# DATN_Schematic.net
KiCad netlist of a schematic drawn in Altium Designer
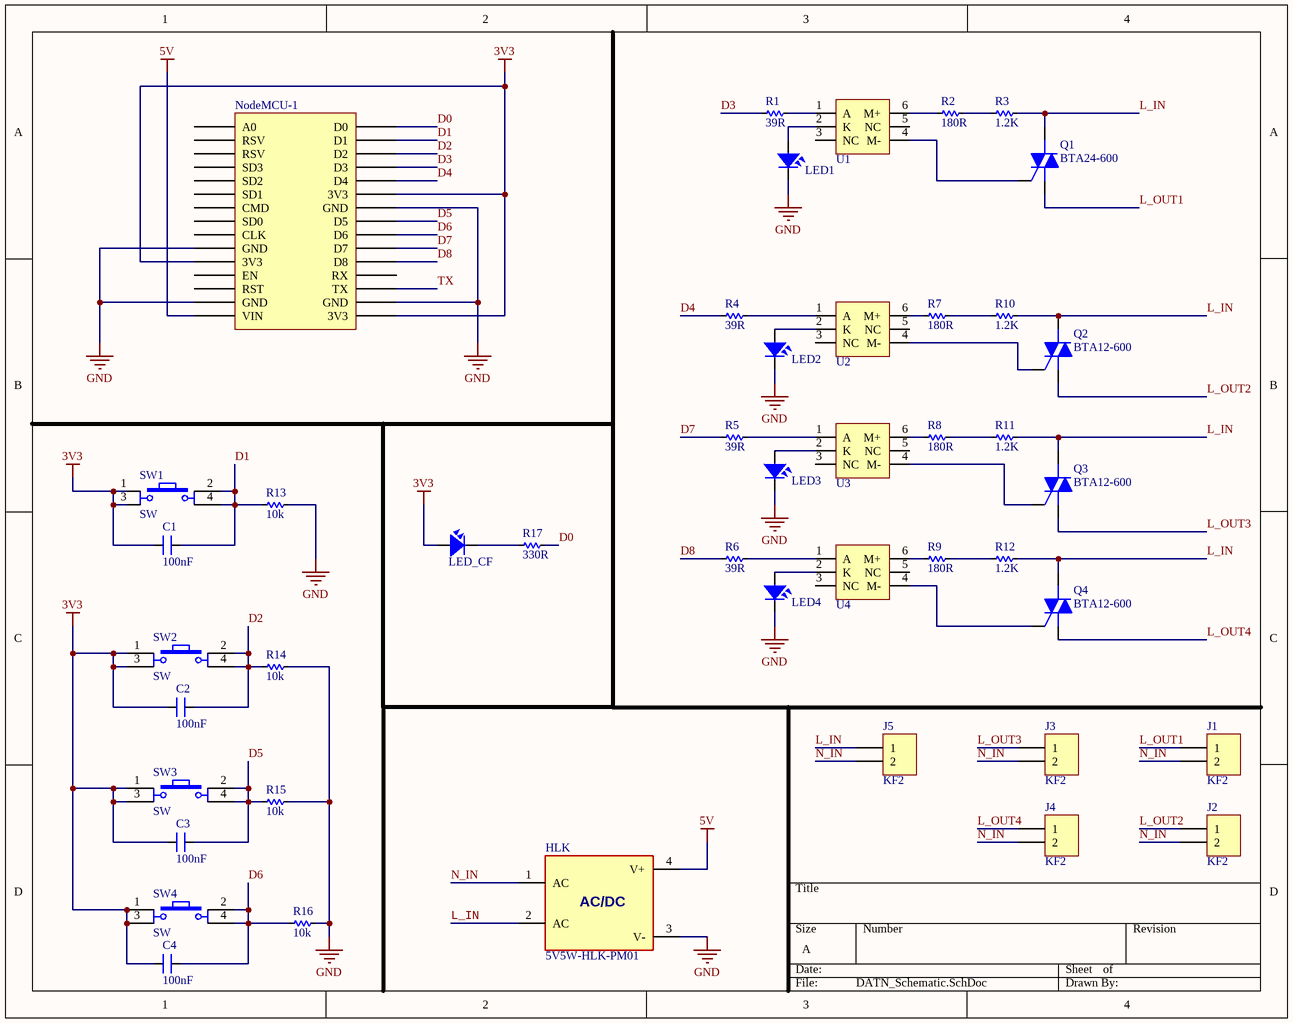
[diagram p0: DATN_Schematic.SchDoc]

(export (version "E")
  (design (tool "Eeschema 10.0.6"))
  (components
    (comp (ref "C1") (value "100nF") (footprint "CN1.5") (libsource (lib "LIBRARY_mualinhkien") (part "CN")))
    (comp (ref "C2") (value "100nF") (footprint "CN1.5") (libsource (lib "LIBRARY_mualinhkien") (part "CN")))
    (comp (ref "C3") (value "100nF") (footprint "CN1.5") (libsource (lib "LIBRARY_mualinhkien") (part "CN")))
    (comp (ref "C4") (value "100nF") (footprint "CN1.5") (libsource (lib "LIBRARY_mualinhkien") (part "CN")))
    (comp (ref "HLK")
      (value "5V5W-HLK-PM01")
      (footprint "HLK_PM01 5V3W")
      (libsource (lib "Duc") (part "5V3W-HLK-PM01"))
    )
    (comp (ref "J1")
      (value "KF2")
      (footprint "KF2-5.08")
      (fields
        (field (name "MANUFACTURER") "Würth Elektronik eiSos GmbH")
        (field (name "PARTNO") "691103110002")
        (field (name "CREATED BY") "Karrer Zheng")
      )
      (libsource (lib "LIBRARY_mualinhkien") (part "KF2"))
    )
    (comp (ref "J2")
      (value "KF2")
      (footprint "KF2-5.08")
      (fields
        (field (name "MANUFACTURER") "Würth Elektronik eiSos GmbH")
        (field (name "PARTNO") "691103110002")
        (field (name "CREATED BY") "Karrer Zheng")
      )
      (libsource (lib "LIBRARY_mualinhkien") (part "KF2"))
    )
    (comp (ref "J3")
      (value "KF2")
      (footprint "KF2-5.08")
      (fields
        (field (name "MANUFACTURER") "Würth Elektronik eiSos GmbH")
        (field (name "PARTNO") "691103110002")
        (field (name "CREATED BY") "Karrer Zheng")
      )
      (libsource (lib "LIBRARY_mualinhkien") (part "KF2"))
    )
    (comp (ref "J4")
      (value "KF2")
      (footprint "KF2-5.08")
      (fields
        (field (name "MANUFACTURER") "Würth Elektronik eiSos GmbH")
        (field (name "PARTNO") "691103110002")
        (field (name "CREATED BY") "Karrer Zheng")
      )
      (libsource (lib "LIBRARY_mualinhkien") (part "KF2"))
    )
    (comp (ref "J5")
      (value "KF2")
      (footprint "KF2-5.08")
      (fields
        (field (name "MANUFACTURER") "Würth Elektronik eiSos GmbH")
        (field (name "PARTNO") "691103110002")
        (field (name "CREATED BY") "Karrer Zheng")
      )
      (libsource (lib "LIBRARY_mualinhkien") (part "KF2"))
    )
    (comp (ref "LED1")
      (value "LED")
      (footprint "LED-5-RED")
      (description "LED Single colour Green and Red")
      (libsource (lib "LIBRARY_mualinhkien") (part "LED"))
    )
    (comp (ref "LED2")
      (value "LED")
      (footprint "LED-5-RED")
      (description "LED Single colour Green and Red")
      (libsource (lib "LIBRARY_mualinhkien") (part "LED"))
    )
    (comp (ref "LED3")
      (value "LED")
      (footprint "LED-5-RED")
      (description "LED Single colour Green and Red")
      (libsource (lib "LIBRARY_mualinhkien") (part "LED"))
    )
    (comp (ref "LED4")
      (value "LED")
      (footprint "LED-5-RED")
      (description "LED Single colour Green and Red")
      (libsource (lib "LIBRARY_mualinhkien") (part "LED"))
    )
    (comp (ref "LED_CF")
      (value "LED")
      (footprint "LED-5MM-BLUE")
      (description "LED Single colour Green and Red")
      (libsource (lib "LIBRARY_mualinhkien") (part "LED"))
    )
    (comp (ref "NodeMCU-1")
      (value "NodeMCU V1.0 ESP-12E")
      (footprint "NodeMCU V1.0 ESP-12E")
      (description "NodeMCU V1.0 ESP8266 (ESP-12E)")
      (libsource (lib "nodemcu") (part "NodeMCU V1.0 ESP-12E"))
    )
    (comp (ref "Q1")
      (value "BTA24-600")
      (footprint "TO220H1")
      (description "Silicon Bidirectional Triode Thyristor")
      (fields (field (name "PUBLISHER") "Altium Limited"))
      (libsource (lib "LIBRARY_mualinhkien") (part "BTA12-600"))
    )
    (comp (ref "Q2")
      (value "BTA12-600")
      (footprint "TO220H1")
      (description "Silicon Bidirectional Triode Thyristor")
      (fields (field (name "PUBLISHER") "Altium Limited"))
      (libsource (lib "LIBRARY_mualinhkien") (part "BTA12-600"))
    )
    (comp (ref "Q3")
      (value "BTA12-600")
      (footprint "TO220H1")
      (description "Silicon Bidirectional Triode Thyristor")
      (fields (field (name "PUBLISHER") "Altium Limited"))
      (libsource (lib "LIBRARY_mualinhkien") (part "BTA12-600"))
    )
    (comp (ref "Q4")
      (value "BTA12-600")
      (footprint "TO220H1")
      (description "Silicon Bidirectional Triode Thyristor")
      (fields (field (name "PUBLISHER") "Altium Limited"))
      (libsource (lib "LIBRARY_mualinhkien") (part "BTA12-600"))
    )
    (comp (ref "R1")
      (value "39R")
      (footprint "RES-1/4W")
      (description "Res")
      (fields
        (field (name "MANUFACTURER") "Generic Components")
        (field (name "PUBLISHER") "Altium Hobart Technology Centre")
      )
      (libsource (lib "LIBRARY_mualinhkien") (part "Res"))
    )
    (comp (ref "R2")
      (value "180R")
      (footprint "RES-1/4W")
      (description "Res")
      (fields
        (field (name "MANUFACTURER") "Generic Components")
        (field (name "PUBLISHER") "Altium Hobart Technology Centre")
      )
      (libsource (lib "LIBRARY_mualinhkien") (part "Res"))
    )
    (comp (ref "R3")
      (value "1.2K")
      (footprint "RES-1/4W")
      (description "Res")
      (fields
        (field (name "MANUFACTURER") "Generic Components")
        (field (name "PUBLISHER") "Altium Hobart Technology Centre")
      )
      (libsource (lib "LIBRARY_mualinhkien") (part "Res"))
    )
    (comp (ref "R4")
      (value "39R")
      (footprint "RES-1/4W")
      (description "Res")
      (fields
        (field (name "MANUFACTURER") "Generic Components")
        (field (name "PUBLISHER") "Altium Hobart Technology Centre")
      )
      (libsource (lib "LIBRARY_mualinhkien") (part "Res"))
    )
    (comp (ref "R5")
      (value "39R")
      (footprint "RES-1/4W")
      (description "Res")
      (fields
        (field (name "MANUFACTURER") "Generic Components")
        (field (name "PUBLISHER") "Altium Hobart Technology Centre")
      )
      (libsource (lib "LIBRARY_mualinhkien") (part "Res"))
    )
    (comp (ref "R6")
      (value "39R")
      (footprint "RES-1/4W")
      (description "Res")
      (fields
        (field (name "MANUFACTURER") "Generic Components")
        (field (name "PUBLISHER") "Altium Hobart Technology Centre")
      )
      (libsource (lib "LIBRARY_mualinhkien") (part "Res"))
    )
    (comp (ref "R7")
      (value "180R")
      (footprint "RES-1/4W")
      (description "Res")
      (fields
        (field (name "MANUFACTURER") "Generic Components")
        (field (name "PUBLISHER") "Altium Hobart Technology Centre")
      )
      (libsource (lib "LIBRARY_mualinhkien") (part "Res"))
    )
    (comp (ref "R8")
      (value "180R")
      (footprint "RES-1/4W")
      (description "Res")
      (fields
        (field (name "MANUFACTURER") "Generic Components")
        (field (name "PUBLISHER") "Altium Hobart Technology Centre")
      )
      (libsource (lib "LIBRARY_mualinhkien") (part "Res"))
    )
    (comp (ref "R9")
      (value "180R")
      (footprint "RES-1/4W")
      (description "Res")
      (fields
        (field (name "MANUFACTURER") "Generic Components")
        (field (name "PUBLISHER") "Altium Hobart Technology Centre")
      )
      (libsource (lib "LIBRARY_mualinhkien") (part "Res"))
    )
    (comp (ref "R10")
      (value "1.2K")
      (footprint "RES-1/4W")
      (description "Res")
      (fields
        (field (name "MANUFACTURER") "Generic Components")
        (field (name "PUBLISHER") "Altium Hobart Technology Centre")
      )
      (libsource (lib "LIBRARY_mualinhkien") (part "Res"))
    )
    (comp (ref "R11")
      (value "1.2K")
      (footprint "RES-1/4W")
      (description "Res")
      (fields
        (field (name "MANUFACTURER") "Generic Components")
        (field (name "PUBLISHER") "Altium Hobart Technology Centre")
      )
      (libsource (lib "LIBRARY_mualinhkien") (part "Res"))
    )
    (comp (ref "R12")
      (value "1.2K")
      (footprint "RES-1/4W")
      (description "Res")
      (fields
        (field (name "MANUFACTURER") "Generic Components")
        (field (name "PUBLISHER") "Altium Hobart Technology Centre")
      )
      (libsource (lib "LIBRARY_mualinhkien") (part "Res"))
    )
    (comp (ref "R13")
      (value "10k")
      (footprint "RES-1/4W")
      (description "Res")
      (fields
        (field (name "MANUFACTURER") "Generic Components")
        (field (name "PUBLISHER") "Altium Hobart Technology Centre")
      )
      (libsource (lib "LIBRARY_mualinhkien") (part "Res"))
    )
    (comp (ref "R14")
      (value "10k")
      (footprint "RES-1/4W")
      (description "Res")
      (fields
        (field (name "MANUFACTURER") "Generic Components")
        (field (name "PUBLISHER") "Altium Hobart Technology Centre")
      )
      (libsource (lib "LIBRARY_mualinhkien") (part "Res"))
    )
    (comp (ref "R15")
      (value "10k")
      (footprint "RES-1/4W")
      (description "Res")
      (fields
        (field (name "MANUFACTURER") "Generic Components")
        (field (name "PUBLISHER") "Altium Hobart Technology Centre")
      )
      (libsource (lib "LIBRARY_mualinhkien") (part "Res"))
    )
    (comp (ref "R16")
      (value "10k")
      (footprint "RES-1/4W")
      (description "Res")
      (fields
        (field (name "MANUFACTURER") "Generic Components")
        (field (name "PUBLISHER") "Altium Hobart Technology Centre")
      )
      (libsource (lib "LIBRARY_mualinhkien") (part "Res"))
    )
    (comp (ref "R17")
      (value "330R")
      (footprint "RES-1/4W")
      (description "Res")
      (fields
        (field (name "MANUFACTURER") "Generic Components")
        (field (name "PUBLISHER") "Altium Hobart Technology Centre")
      )
      (libsource (lib "LIBRARY_mualinhkien") (part "Res"))
    )
    (comp (ref "SW1")
      (value "SW")
      (footprint "SW4B")
      (description "Switch button 4 pin")
      (libsource (lib "syhaunguyen") (part "SW4"))
    )
    (comp (ref "SW2")
      (value "SW")
      (footprint "SW4B")
      (description "Switch button 4 pin")
      (libsource (lib "syhaunguyen") (part "SW4"))
    )
    (comp (ref "SW3")
      (value "SW")
      (footprint "SW4B")
      (description "Switch button 4 pin")
      (libsource (lib "syhaunguyen") (part "SW4"))
    )
    (comp (ref "SW4")
      (value "SW")
      (footprint "SW4B")
      (description "Switch button 4 pin")
      (libsource (lib "syhaunguyen") (part "SW4"))
    )
    (comp (ref "U1")
      (value "MOC3021M")
      (footprint "DIP6")
      (libsource (lib "LIBRARY_mualinhkien") (part "MOC3021M"))
    )
    (comp (ref "U2")
      (value "MOC3021M")
      (footprint "DIP6")
      (libsource (lib "LIBRARY_mualinhkien") (part "MOC3021M"))
    )
    (comp (ref "U3")
      (value "MOC3021M")
      (footprint "DIP6")
      (libsource (lib "LIBRARY_mualinhkien") (part "MOC3021M"))
    )
    (comp (ref "U4")
      (value "MOC3021M")
      (footprint "DIP6")
      (libsource (lib "LIBRARY_mualinhkien") (part "MOC3021M"))
    )
  )
  (nets
    (net (code "1") (name "/D0") (class "Default")
      (node (ref "NodeMCU-1") (pin "D0") (pinfunction "D0_D0") (pintype "passive"))
      (node (ref "R17") (pin "1") (pinfunction "1_1") (pintype "passive"))
    )
    (net (code "2") (name "/D1") (class "Default")
      (node (ref "C1") (pin "2") (pinfunction "2_2") (pintype "passive"))
      (node (ref "NodeMCU-1") (pin "D1") (pinfunction "D1_D1") (pintype "passive"))
      (node (ref "R13") (pin "1") (pinfunction "1_1") (pintype "passive"))
      (node (ref "SW1") (pin "2") (pintype "passive"))
      (node (ref "SW1") (pin "4") (pintype "passive"))
    )
    (net (code "3") (name "/D2") (class "Default")
      (node (ref "C2") (pin "2") (pinfunction "2_2") (pintype "passive"))
      (node (ref "NodeMCU-1") (pin "D2") (pinfunction "D2_D2") (pintype "passive"))
      (node (ref "R14") (pin "1") (pinfunction "1_1") (pintype "passive"))
      (node (ref "SW2") (pin "2") (pintype "passive"))
      (node (ref "SW2") (pin "4") (pintype "passive"))
    )
    (net (code "4") (name "/D3") (class "Default")
      (node (ref "NodeMCU-1") (pin "D3") (pinfunction "D3_D3") (pintype "passive"))
      (node (ref "R1") (pin "2") (pinfunction "2_2") (pintype "passive"))
    )
    (net (code "5") (name "/D4") (class "Default")
      (node (ref "NodeMCU-1") (pin "D4") (pinfunction "D4_D4") (pintype "passive"))
      (node (ref "R4") (pin "2") (pinfunction "2_2") (pintype "passive"))
    )
    (net (code "6") (name "/D5") (class "Default")
      (node (ref "C3") (pin "2") (pinfunction "2_2") (pintype "passive"))
      (node (ref "NodeMCU-1") (pin "D5") (pinfunction "D5_D5") (pintype "passive"))
      (node (ref "R15") (pin "1") (pinfunction "1_1") (pintype "passive"))
      (node (ref "SW3") (pin "2") (pintype "passive"))
      (node (ref "SW3") (pin "4") (pintype "passive"))
    )
    (net (code "7") (name "/D6") (class "Default")
      (node (ref "C4") (pin "2") (pinfunction "2_2") (pintype "passive"))
      (node (ref "NodeMCU-1") (pin "D6") (pinfunction "D6_D6") (pintype "passive"))
      (node (ref "R16") (pin "1") (pinfunction "1_1") (pintype "passive"))
      (node (ref "SW4") (pin "2") (pintype "passive"))
      (node (ref "SW4") (pin "4") (pintype "passive"))
    )
    (net (code "8") (name "/D7") (class "Default")
      (node (ref "NodeMCU-1") (pin "D7") (pinfunction "D7_D7") (pintype "passive"))
      (node (ref "R5") (pin "2") (pinfunction "2_2") (pintype "passive"))
    )
    (net (code "9") (name "/D8") (class "Default")
      (node (ref "NodeMCU-1") (pin "D8") (pinfunction "D8_D8") (pintype "passive"))
      (node (ref "R6") (pin "2") (pinfunction "2_2") (pintype "passive"))
    )
    (net (code "10") (name "/L_IN") (class "Default")
      (node (ref "HLK") (pin "2") (pinfunction "AC_2") (pintype "passive"))
      (node (ref "J5") (pin "1") (pinfunction "1_1") (pintype "passive"))
      (node (ref "Q1") (pin "2") (pinfunction "M2_2") (pintype "passive"))
      (node (ref "Q2") (pin "2") (pinfunction "M2_2") (pintype "passive"))
      (node (ref "Q3") (pin "2") (pinfunction "M2_2") (pintype "passive"))
      (node (ref "Q4") (pin "2") (pinfunction "M2_2") (pintype "passive"))
      (node (ref "R10") (pin "1") (pinfunction "1_1") (pintype "passive"))
      (node (ref "R11") (pin "1") (pinfunction "1_1") (pintype "passive"))
      (node (ref "R12") (pin "1") (pinfunction "1_1") (pintype "passive"))
      (node (ref "R3") (pin "1") (pinfunction "1_1") (pintype "passive"))
    )
    (net (code "11") (name "/L_OUT1") (class "Default")
      (node (ref "J1") (pin "1") (pinfunction "1_1") (pintype "passive"))
      (node (ref "Q1") (pin "1") (pinfunction "M1_1") (pintype "passive"))
    )
    (net (code "12") (name "/L_OUT2") (class "Default")
      (node (ref "J2") (pin "1") (pinfunction "1_1") (pintype "passive"))
      (node (ref "Q2") (pin "1") (pinfunction "M1_1") (pintype "passive"))
    )
    (net (code "13") (name "/L_OUT3") (class "Default")
      (node (ref "J3") (pin "1") (pinfunction "1_1") (pintype "passive"))
      (node (ref "Q3") (pin "1") (pinfunction "M1_1") (pintype "passive"))
    )
    (net (code "14") (name "/L_OUT4") (class "Default")
      (node (ref "J4") (pin "1") (pinfunction "1_1") (pintype "passive"))
      (node (ref "Q4") (pin "1") (pinfunction "M1_1") (pintype "passive"))
    )
    (net (code "15") (name "/N_IN") (class "Default")
      (node (ref "HLK") (pin "1") (pinfunction "AC_1") (pintype "passive"))
      (node (ref "J1") (pin "2") (pinfunction "2_2") (pintype "passive"))
      (node (ref "J2") (pin "2") (pinfunction "2_2") (pintype "passive"))
      (node (ref "J3") (pin "2") (pinfunction "2_2") (pintype "passive"))
      (node (ref "J4") (pin "2") (pinfunction "2_2") (pintype "passive"))
      (node (ref "J5") (pin "2") (pinfunction "2_2") (pintype "passive"))
    )
    (net (code "16") (name "/TX") (class "Default")
      (node (ref "NodeMCU-1") (pin "TX") (pinfunction "TX_TX") (pintype "passive"))
    )
    (net (code "17") (name "3V3") (class "Default")
      (node (ref "C1") (pin "1") (pinfunction "1_1") (pintype "passive"))
      (node (ref "C2") (pin "1") (pinfunction "1_1") (pintype "passive"))
      (node (ref "C3") (pin "1") (pinfunction "1_1") (pintype "passive"))
      (node (ref "C4") (pin "1") (pinfunction "1_1") (pintype "passive"))
      (node (ref "LED_CF") (pin "1") (pinfunction "1_1") (pintype "passive"))
      (node (ref "NodeMCU-1") (pin "3V3") (pinfunction "3V3_3V3") (pintype "passive"))
      (node (ref "SW1") (pin "1") (pintype "passive"))
      (node (ref "SW1") (pin "3") (pintype "passive"))
      (node (ref "SW2") (pin "1") (pintype "passive"))
      (node (ref "SW2") (pin "3") (pintype "passive"))
      (node (ref "SW3") (pin "1") (pintype "passive"))
      (node (ref "SW3") (pin "3") (pintype "passive"))
      (node (ref "SW4") (pin "1") (pintype "passive"))
      (node (ref "SW4") (pin "3") (pintype "passive"))
    )
    (net (code "18") (name "5V") (class "Default")
      (node (ref "HLK") (pin "4") (pinfunction "V+_4") (pintype "passive"))
      (node (ref "NodeMCU-1") (pin "VIN") (pinfunction "VIN_VIN") (pintype "passive"))
    )
    (net (code "19") (name "GND") (class "Default")
      (node (ref "HLK") (pin "3") (pinfunction "V-_3") (pintype "passive"))
      (node (ref "LED1") (pin "2") (pinfunction "2_2") (pintype "passive"))
      (node (ref "LED2") (pin "2") (pinfunction "2_2") (pintype "passive"))
      (node (ref "LED3") (pin "2") (pinfunction "2_2") (pintype "passive"))
      (node (ref "LED4") (pin "2") (pinfunction "2_2") (pintype "passive"))
      (node (ref "NodeMCU-1") (pin "GND") (pinfunction "GND_GND") (pintype "passive"))
      (node (ref "R13") (pin "2") (pinfunction "2_2") (pintype "passive"))
      (node (ref "R14") (pin "2") (pinfunction "2_2") (pintype "passive"))
      (node (ref "R15") (pin "2") (pinfunction "2_2") (pintype "passive"))
      (node (ref "R16") (pin "2") (pinfunction "2_2") (pintype "passive"))
    )
    (net (code "20") (name "Net-(LED_CF-Pad2)") (class "Default")
      (node (ref "LED_CF") (pin "2") (pinfunction "2_2") (pintype "passive"))
      (node (ref "R17") (pin "2") (pinfunction "2_2") (pintype "passive"))
    )
    (net (code "21") (name "Net-(Q1-G)") (class "Default")
      (node (ref "Q1") (pin "3") (pinfunction "G_3") (pintype "passive"))
      (node (ref "U1") (pin "4") (pinfunction "M-_4") (pintype "passive"))
    )
    (net (code "22") (name "Net-(Q2-G)") (class "Default")
      (node (ref "Q2") (pin "3") (pinfunction "G_3") (pintype "passive"))
      (node (ref "U2") (pin "4") (pinfunction "M-_4") (pintype "passive"))
    )
    (net (code "23") (name "Net-(Q3-G)") (class "Default")
      (node (ref "Q3") (pin "3") (pinfunction "G_3") (pintype "passive"))
      (node (ref "U3") (pin "4") (pinfunction "M-_4") (pintype "passive"))
    )
    (net (code "24") (name "Net-(Q4-G)") (class "Default")
      (node (ref "Q4") (pin "3") (pinfunction "G_3") (pintype "passive"))
      (node (ref "U4") (pin "4") (pinfunction "M-_4") (pintype "passive"))
    )
    (net (code "25") (name "Net-(R2-Pad1)") (class "Default")
      (node (ref "R2") (pin "1") (pinfunction "1_1") (pintype "passive"))
      (node (ref "R3") (pin "2") (pinfunction "2_2") (pintype "passive"))
    )
    (net (code "26") (name "Net-(R10-Pad2)") (class "Default")
      (node (ref "R10") (pin "2") (pinfunction "2_2") (pintype "passive"))
      (node (ref "R7") (pin "1") (pinfunction "1_1") (pintype "passive"))
    )
    (net (code "27") (name "Net-(R11-Pad2)") (class "Default")
      (node (ref "R11") (pin "2") (pinfunction "2_2") (pintype "passive"))
      (node (ref "R8") (pin "1") (pinfunction "1_1") (pintype "passive"))
    )
    (net (code "28") (name "Net-(R12-Pad2)") (class "Default")
      (node (ref "R12") (pin "2") (pinfunction "2_2") (pintype "passive"))
      (node (ref "R9") (pin "1") (pinfunction "1_1") (pintype "passive"))
    )
    (net (code "29") (name "Net-(U1-A)") (class "Default")
      (node (ref "R1") (pin "1") (pinfunction "1_1") (pintype "passive"))
      (node (ref "U1") (pin "1") (pinfunction "A_1") (pintype "passive"))
    )
    (net (code "30") (name "Net-(U1-K)") (class "Default")
      (node (ref "LED1") (pin "1") (pinfunction "1_1") (pintype "passive"))
      (node (ref "U1") (pin "2") (pinfunction "K_2") (pintype "passive"))
    )
    (net (code "31") (name "Net-(U1-M+)") (class "Default")
      (node (ref "R2") (pin "2") (pinfunction "2_2") (pintype "passive"))
      (node (ref "U1") (pin "6") (pinfunction "M+_6") (pintype "passive"))
    )
    (net (code "32") (name "Net-(U2-A)") (class "Default")
      (node (ref "R4") (pin "1") (pinfunction "1_1") (pintype "passive"))
      (node (ref "U2") (pin "1") (pinfunction "A_1") (pintype "passive"))
    )
    (net (code "33") (name "Net-(U2-K)") (class "Default")
      (node (ref "LED2") (pin "1") (pinfunction "1_1") (pintype "passive"))
      (node (ref "U2") (pin "2") (pinfunction "K_2") (pintype "passive"))
    )
    (net (code "34") (name "Net-(U2-M+)") (class "Default")
      (node (ref "R7") (pin "2") (pinfunction "2_2") (pintype "passive"))
      (node (ref "U2") (pin "6") (pinfunction "M+_6") (pintype "passive"))
    )
    (net (code "35") (name "Net-(U3-A)") (class "Default")
      (node (ref "R5") (pin "1") (pinfunction "1_1") (pintype "passive"))
      (node (ref "U3") (pin "1") (pinfunction "A_1") (pintype "passive"))
    )
    (net (code "36") (name "Net-(U3-K)") (class "Default")
      (node (ref "LED3") (pin "1") (pinfunction "1_1") (pintype "passive"))
      (node (ref "U3") (pin "2") (pinfunction "K_2") (pintype "passive"))
    )
    (net (code "37") (name "Net-(U3-M+)") (class "Default")
      (node (ref "R8") (pin "2") (pinfunction "2_2") (pintype "passive"))
      (node (ref "U3") (pin "6") (pinfunction "M+_6") (pintype "passive"))
    )
    (net (code "38") (name "Net-(U4-A)") (class "Default")
      (node (ref "R6") (pin "1") (pinfunction "1_1") (pintype "passive"))
      (node (ref "U4") (pin "1") (pinfunction "A_1") (pintype "passive"))
    )
    (net (code "39") (name "Net-(U4-K)") (class "Default")
      (node (ref "LED4") (pin "1") (pinfunction "1_1") (pintype "passive"))
      (node (ref "U4") (pin "2") (pinfunction "K_2") (pintype "passive"))
    )
    (net (code "40") (name "Net-(U4-M+)") (class "Default")
      (node (ref "R9") (pin "2") (pinfunction "2_2") (pintype "passive"))
      (node (ref "U4") (pin "6") (pinfunction "M+_6") (pintype "passive"))
    )
    (net (code "41") (name "unconnected-(NodeMCU-1-PadA0)") (class "Default")
      (node (ref "NodeMCU-1") (pin "A0") (pinfunction "A0_A0") (pintype "passive"))
    )
    (net (code "42") (name "unconnected-(NodeMCU-1-PadCLK)") (class "Default")
      (node (ref "NodeMCU-1") (pin "CLK") (pinfunction "CLK_CLK") (pintype "passive"))
    )
    (net (code "43") (name "unconnected-(NodeMCU-1-PadCMD)") (class "Default")
      (node (ref "NodeMCU-1") (pin "CMD") (pinfunction "CMD_CMD") (pintype "passive"))
    )
    (net (code "44") (name "unconnected-(NodeMCU-1-PadEN)") (class "Default")
      (node (ref "NodeMCU-1") (pin "EN") (pinfunction "EN_EN") (pintype "passive"))
    )
    (net (code "45") (name "unconnected-(NodeMCU-1-PadRST)") (class "Default")
      (node (ref "NodeMCU-1") (pin "RST") (pinfunction "RST_RST") (pintype "passive"))
    )
    (net (code "46") (name "unconnected-(NodeMCU-1-PadRSV)") (class "Default")
      (node (ref "NodeMCU-1") (pin "RSV") (pinfunction "RSV_RSV") (pintype "passive"))
    )
    (net (code "47") (name "unconnected-(NodeMCU-1-PadRSV)_1") (class "Default")
      (node (ref "NodeMCU-1") (pin "RSV") (pinfunction "RSV_RSV") (pintype "passive"))
    )
    (net (code "48") (name "unconnected-(NodeMCU-1-PadRX)") (class "Default")
      (node (ref "NodeMCU-1") (pin "RX") (pinfunction "RX_RX") (pintype "passive"))
    )
    (net (code "49") (name "unconnected-(NodeMCU-1-PadSD0)") (class "Default")
      (node (ref "NodeMCU-1") (pin "SD0") (pinfunction "SD0_SD0") (pintype "passive"))
    )
    (net (code "50") (name "unconnected-(NodeMCU-1-PadSD1)") (class "Default")
      (node (ref "NodeMCU-1") (pin "SD1") (pinfunction "SD1_SD1") (pintype "passive"))
    )
    (net (code "51") (name "unconnected-(NodeMCU-1-PadSD2)") (class "Default")
      (node (ref "NodeMCU-1") (pin "SD2") (pinfunction "SD2_SD2") (pintype "passive"))
    )
    (net (code "52") (name "unconnected-(NodeMCU-1-PadSD3)") (class "Default")
      (node (ref "NodeMCU-1") (pin "SD3") (pinfunction "SD3_SD3") (pintype "passive"))
    )
    (net (code "53") (name "unconnected-(U1-NC-Pad3)") (class "Default")
      (node (ref "U1") (pin "3") (pinfunction "NC_3") (pintype "passive"))
    )
    (net (code "54") (name "unconnected-(U1-NC-Pad5)") (class "Default")
      (node (ref "U1") (pin "5") (pinfunction "NC_5") (pintype "passive"))
    )
    (net (code "55") (name "unconnected-(U2-NC-Pad3)") (class "Default")
      (node (ref "U2") (pin "3") (pinfunction "NC_3") (pintype "passive"))
    )
    (net (code "56") (name "unconnected-(U2-NC-Pad5)") (class "Default")
      (node (ref "U2") (pin "5") (pinfunction "NC_5") (pintype "passive"))
    )
    (net (code "57") (name "unconnected-(U3-NC-Pad3)") (class "Default")
      (node (ref "U3") (pin "3") (pinfunction "NC_3") (pintype "passive"))
    )
    (net (code "58") (name "unconnected-(U3-NC-Pad5)") (class "Default")
      (node (ref "U3") (pin "5") (pinfunction "NC_5") (pintype "passive"))
    )
    (net (code "59") (name "unconnected-(U4-NC-Pad3)") (class "Default")
      (node (ref "U4") (pin "3") (pinfunction "NC_3") (pintype "passive"))
    )
    (net (code "60") (name "unconnected-(U4-NC-Pad5)") (class "Default")
      (node (ref "U4") (pin "5") (pinfunction "NC_5") (pintype "passive"))
    )
  )
)
